# DClink.net
KiCad netlist of a schematic drawn in Altium Designer
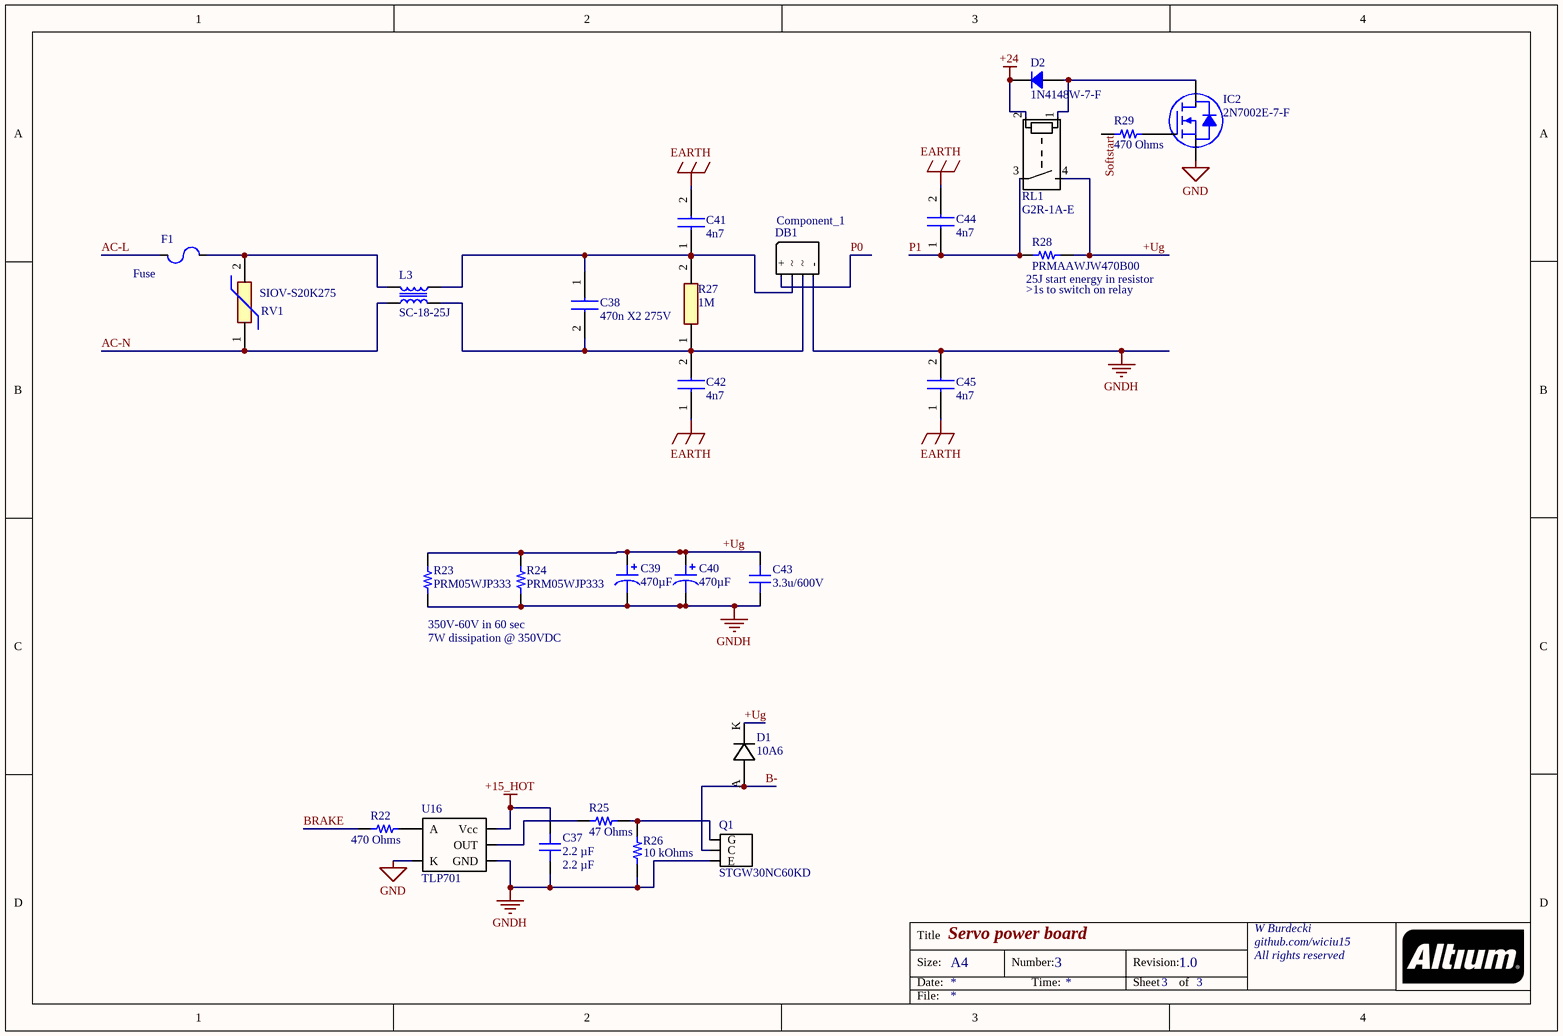
[diagram p0: DClink.SchDoc]

(export (version "E")
  (design (tool "Eeschema 10.0.6"))
  (components
    (comp (ref "C37")
      (value "2.2 µF")
      (footprint "CAP 0805_2012")
      (description "CAP CER 2.2UF 35V X7R 0805")
      (fields
        (field (name "PART NUMBER") "C2012X7R1V225K125AB")
        (field (name "ALTIUM_VALUE") "2.2 µF")
        (field (name "MANUFACTURER") "TDK Corporation")
      )
      (libsource (lib "Celestial") (part "Capacitor"))
    )
    (comp (ref "C38")
      (value "470n X2 275V")
      (footprint "SamacSys:R46KI347050M1K")
      (description "KEMET R46KI347050M1K")
      (fields
        (field (name "MANUFACTURER_PART_NUMBER") "R46KI347050M1K")
        (field (name "MOUSER PART NUMBER") "80-R46KI347050M1K")
      )
      (libsource (lib "*") (part "R46KI347050M1K"))
    )
    (comp (ref "C39")
      (value "470µF")
      (footprint "CAP TH ALUM ELEC D35.00mm S10.00mm H47.00mm")
      (description "CAP ALUM 470UF 20% 450V SNAP")
      (fields (field (name "PART NUMBER") "450HXG470MEFCSN35X45") (field (name "MANUFACTURER") "Rubycon"))
      (libsource (lib "Celestial") (part "Polarised Capacitor"))
    )
    (comp (ref "C40")
      (value "470µF")
      (footprint "CAP TH ALUM ELEC D35.00mm S10.00mm H47.00mm")
      (description "CAP ALUM 470UF 20% 450V SNAP")
      (fields (field (name "PART NUMBER") "450HXG470MEFCSN35X45") (field (name "MANUFACTURER") "Rubycon"))
      (libsource (lib "Celestial") (part "Polarised Capacitor"))
    )
    (comp (ref "C41")
      (value "4n7")
      (footprint "SamacSys:B32021_(13_x_5)")
      (description "B32021A3472")
      (fields
        (field (name "MANUFACTURER_PART_NUMBER") "B32021A3472K289")
        (field (name "MOUSER PART NUMBER") "871-B32021A3472K289")
      )
      (libsource (lib "*") (part "B32021A3472K289"))
    )
    (comp (ref "C42")
      (value "4n7")
      (footprint "SamacSys:B32021_(13_x_5)")
      (description "B32021A3472")
      (fields
        (field (name "MANUFACTURER_PART_NUMBER") "B32021A3472K289")
        (field (name "MOUSER PART NUMBER") "871-B32021A3472K289")
      )
      (libsource (lib "*") (part "B32021A3472K289"))
    )
    (comp (ref "C43")
      (value "3.3u/600V")
      (footprint "C4AQHBU4330P1WJ")
      (libsource (lib "C4AQHBU4330P1WJ") (part "3.3u/600V"))
    )
    (comp (ref "C44")
      (value "4n7")
      (footprint "SamacSys:B32021_(13_x_5)")
      (description "B32021A3472")
      (fields
        (field (name "MANUFACTURER_PART_NUMBER") "B32021A3472K289")
        (field (name "MOUSER PART NUMBER") "871-B32021A3472K289")
      )
      (libsource (lib "*") (part "B32021A3472K289"))
    )
    (comp (ref "C45")
      (value "4n7")
      (footprint "SamacSys:B32021_(13_x_5)")
      (description "B32021A3472")
      (fields
        (field (name "MANUFACTURER_PART_NUMBER") "B32021A3472K289")
        (field (name "MOUSER PART NUMBER") "871-B32021A3472K289")
      )
      (libsource (lib "*") (part "B32021A3472K289"))
    )
    (comp (ref "D1") (value "10A6") (footprint "10A6") (libsource (lib "10A6") (part "10A6")))
    (comp (ref "D2")
      (value "1N4148W-7-F")
      (footprint "SOD-123")
      (description "DIODE GEN PURP 100V 300MA SOD123")
      (fields (field (name "MANUFACTURER") "Diodes Incorporated"))
      (libsource (lib "Celestial") (part "Diode"))
    )
    (comp (ref "DB1")
      (value "Component_1")
      (footprint "GBJ2506")
      (libsource (lib "GBJ2506") (part "Component_1"))
    )
    (comp (ref "F1")
      (value "Fuse")
      (footprint "FUSE")
      (description "Fuse holder 04450001N")
      (libsource (lib "FUSE 04450001N") (part "Fuse"))
    )
    (comp (ref "IC2")
      (value "2N7002E-7-F")
      (footprint "DIODES SOT-23-3")
      (description "MOSFET N-CH 60V 0.25A SOT23-3")
      (fields (field (name "MANUFACTURER") "Diodes Incorporated"))
      (libsource (lib "Celestial") (part "DIODES INC MOSFET N-CH SOT-23-3"))
    )
    (comp (ref "L3")
      (value "SC-18-25J")
      (footprint "SC18-25J")
      (description "https://www.tme.eu/pl/details/sc-18-25j/dlawiki-pierscieniowe/kemet/")
      (libsource (lib "SC18-25J") (part "SC-18-25J"))
    )
    (comp (ref "Q1")
      (value "STGW30NC60KD")
      (footprint "STGW30NC60KD")
      (libsource (lib "STGW30NC60KD") (part "STGW30NC60KD"))
    )
    (comp (ref "R22")
      (value "470 Ohms")
      (footprint "RES 0805_2012")
      (description "RES SMD 470 OHM 0.1% 1/4W 0805")
      (fields
        (field (name "PART NUMBER") "ERJ-PB6B4700V")
        (field (name "MANUFACTURER") "Panasonic Electronic Components")
      )
      (libsource (lib "Celestial") (part "Resistor"))
    )
    (comp (ref "R23")
      (value "PRM05WJP333")
      (footprint "prmaawjw470b00")
      (libsource (lib "CRL5W-33k") (part "PRM05WJP333"))
    )
    (comp (ref "R24")
      (value "PRM05WJP333")
      (footprint "prmaawjw470b00")
      (libsource (lib "CRL5W-33k") (part "PRM05WJP333"))
    )
    (comp (ref "R25")
      (value "47 Ohms")
      (footprint "RES 0805_2012")
      (description "RES 47 OHM 1% 1/3W 0805")
      (fields
        (field (name "PART NUMBER") "CRGP0805F47R")
        (field (name "MANUFACTURER") "TE Connectivity Passive Product")
      )
      (libsource (lib "Celestial") (part "Resistor"))
    )
    (comp (ref "R26")
      (value "10 kOhms")
      (footprint "RES 0805_2012")
      (description "RES 10K OHM 0.1% 1/10W 0805")
      (fields
        (field (name "PART NUMBER") "RNCS0805BKE10K0")
        (field (name "MANUFACTURER") "Stackpole Electronics Inc")
      )
      (libsource (lib "Celestial") (part "Resistor"))
    )
    (comp (ref "R27")
      (value "1M")
      (footprint "SamacSys:RESAD2400W75L1000D350")
      (description "Resistor")
      (fields
        (field (name "MANUFACTURER_PART_NUMBER") "ROX1SJ330K")
        (field (name "MOUSER PART NUMBER") "279-ROX1SJ330K")
      )
      (libsource (lib "*") (part "ROX1SJ330K"))
    )
    (comp (ref "R28")
      (value "PRMAAWJW470B00")
      (footprint "prmaawjw470b00")
      (description "https://www.tme.eu/pl/details/ax10wv-47r/rezystory-mocy/royal-ohm/prmaawjw470b00/")
      (libsource (lib "prmaawjw470b00") (part "PRMAAWJW470B00"))
    )
    (comp (ref "R29")
      (value "470 Ohms")
      (footprint "RES 0805_2012")
      (description "RES SMD 470 OHM 0.1% 1/4W 0805")
      (fields
        (field (name "PART NUMBER") "ERJ-PB6B4700V")
        (field (name "MANUFACTURER") "Panasonic Electronic Components")
      )
      (libsource (lib "Celestial") (part "Resistor"))
    )
    (comp (ref "RL1")
      (value "G2R-1A-E")
      (footprint "G2R-1A-E")
      (libsource (lib "G2R-1A-E") (part "G2R-1A-E"))
    )
    (comp (ref "RV1")
      (value "SIOV-S20K275")
      (footprint "SamacSys:B72220Q0271K101")
      (description "B72220S0271K101")
      (fields
        (field (name "MANUFACTURER_PART_NUMBER") "B72220Q0271K101")
        (field (name "MOUSER PART NUMBER") "871-B72220Q271K101")
      )
      (libsource (lib "*") (part "B72220Q0271K101"))
    )
    (comp (ref "U16")
      (value "TLP701")
      (footprint "TLP701")
      (libsource (lib "Toshiba optocoupler") (part "TLP701"))
    )
  )
  (nets
    (net (code "1") (name "+15_HOT") (class "Default")
      (node (ref "C37") (pin "2") (pinfunction "2_2") (pintype "passive"))
      (node (ref "U16") (pin "6") (pinfunction "Vcc_6") (pintype "passive"))
    )
    (net (code "2") (name "+24") (class "Default")
      (node (ref "D2") (pin "2") (pinfunction "2_2") (pintype "passive"))
      (node (ref "RL1") (pin "2") (pinfunction "2_2") (pintype "passive"))
    )
    (net (code "3") (name "/+Ug") (class "Default")
      (node (ref "C39") (pin "1") (pinfunction "1_1") (pintype "passive"))
      (node (ref "C40") (pin "1") (pinfunction "1_1") (pintype "passive"))
      (node (ref "C43") (pin "2") (pinfunction "2_2") (pintype "passive"))
      (node (ref "D1") (pin "K") (pintype "passive"))
      (node (ref "R23") (pin "2") (pinfunction "2_2") (pintype "passive"))
      (node (ref "R24") (pin "2") (pinfunction "2_2") (pintype "passive"))
      (node (ref "R28") (pin "2") (pinfunction "2_2") (pintype "passive"))
      (node (ref "RL1") (pin "4") (pinfunction "4_4") (pintype "passive"))
    )
    (net (code "4") (name "/AC-L") (class "Default")
      (node (ref "F1") (pin "1") (pinfunction "1_1") (pintype "passive"))
    )
    (net (code "5") (name "/AC-N") (class "Default")
      (node (ref "L3") (pin "1") (pinfunction "1_1") (pintype "passive"))
      (node (ref "RV1") (pin "1") (pinfunction "1_1") (pintype "passive"))
    )
    (net (code "6") (name "/B-") (class "Default")
      (node (ref "D1") (pin "A") (pintype "passive"))
      (node (ref "Q1") (pin "2") (pinfunction "C_2") (pintype "passive"))
    )
    (net (code "7") (name "/BRAKE") (class "Default")
      (node (ref "R22") (pin "1") (pinfunction "1_1") (pintype "passive"))
    )
    (net (code "8") (name "/P0") (class "Default")
      (node (ref "DB1") (pin "1") (pinfunction "+_1") (pintype "passive"))
    )
    (net (code "9") (name "/P1") (class "Default")
      (node (ref "C44") (pin "1") (pinfunction "1_1") (pintype "passive"))
      (node (ref "R28") (pin "1") (pinfunction "1_1") (pintype "passive"))
      (node (ref "RL1") (pin "3") (pinfunction "3_3") (pintype "passive"))
    )
    (net (code "10") (name "/Softstart") (class "Default")
      (node (ref "R29") (pin "1") (pinfunction "1_1") (pintype "passive"))
    )
    (net (code "11") (name "EARTH") (class "Default")
      (node (ref "C41") (pin "2") (pinfunction "2_2") (pintype "passive"))
      (node (ref "C42") (pin "1") (pinfunction "1_1") (pintype "passive"))
      (node (ref "C44") (pin "2") (pinfunction "2_2") (pintype "passive"))
      (node (ref "C45") (pin "1") (pinfunction "1_1") (pintype "passive"))
    )
    (net (code "12") (name "GND") (class "Default")
      (node (ref "IC2") (pin "2") (pinfunction "S_2") (pintype "passive"))
      (node (ref "U16") (pin "3") (pinfunction "K_3") (pintype "passive"))
    )
    (net (code "13") (name "GNDH") (class "Default")
      (node (ref "C37") (pin "1") (pinfunction "1_1") (pintype "passive"))
      (node (ref "C39") (pin "2") (pinfunction "2_2") (pintype "passive"))
      (node (ref "C40") (pin "2") (pinfunction "2_2") (pintype "passive"))
      (node (ref "C43") (pin "1") (pinfunction "1_1") (pintype "passive"))
      (node (ref "C45") (pin "2") (pinfunction "2_2") (pintype "passive"))
      (node (ref "DB1") (pin "4") (pinfunction "-_4") (pintype "passive"))
      (node (ref "Q1") (pin "3") (pinfunction "E_3") (pintype "passive"))
      (node (ref "R23") (pin "1") (pinfunction "1_1") (pintype "passive"))
      (node (ref "R24") (pin "1") (pinfunction "1_1") (pintype "passive"))
      (node (ref "R26") (pin "1") (pinfunction "1_1") (pintype "passive"))
      (node (ref "U16") (pin "4") (pinfunction "GND_4") (pintype "passive"))
    )
    (net (code "14") (name "Net-(C38-Pad1)") (class "Default")
      (node (ref "C38") (pin "1") (pinfunction "1_1") (pintype "passive"))
      (node (ref "C41") (pin "1") (pinfunction "1_1") (pintype "passive"))
      (node (ref "DB1") (pin "2") (pinfunction "~_2") (pintype "passive"))
      (node (ref "L3") (pin "4") (pinfunction "4_4") (pintype "passive"))
      (node (ref "R27") (pin "2") (pinfunction "2_2") (pintype "passive"))
    )
    (net (code "15") (name "Net-(C38-Pad2)") (class "Default")
      (node (ref "C38") (pin "2") (pinfunction "2_2") (pintype "passive"))
      (node (ref "C42") (pin "2") (pinfunction "2_2") (pintype "passive"))
      (node (ref "DB1") (pin "3") (pinfunction "~_3") (pintype "passive"))
      (node (ref "L3") (pin "2") (pinfunction "2_2") (pintype "passive"))
      (node (ref "R27") (pin "1") (pinfunction "1_1") (pintype "passive"))
    )
    (net (code "16") (name "Net-(F1-Pad2)") (class "Default")
      (node (ref "F1") (pin "2") (pinfunction "2_2") (pintype "passive"))
      (node (ref "L3") (pin "3") (pinfunction "3_3") (pintype "passive"))
      (node (ref "RV1") (pin "2") (pinfunction "2_2") (pintype "passive"))
    )
    (net (code "17") (name "Net-(IC2-D)") (class "Default")
      (node (ref "D2") (pin "1") (pinfunction "1_1") (pintype "passive"))
      (node (ref "IC2") (pin "3") (pinfunction "D_3") (pintype "passive"))
      (node (ref "RL1") (pin "1") (pinfunction "1_1") (pintype "passive"))
    )
    (net (code "18") (name "Net-(IC2-G)") (class "Default")
      (node (ref "IC2") (pin "1") (pinfunction "G_1") (pintype "passive"))
      (node (ref "R29") (pin "2") (pinfunction "2_2") (pintype "passive"))
    )
    (net (code "19") (name "Net-(Q1-G)") (class "Default")
      (node (ref "Q1") (pin "1") (pinfunction "G_1") (pintype "passive"))
      (node (ref "R25") (pin "2") (pinfunction "2_2") (pintype "passive"))
      (node (ref "R26") (pin "2") (pinfunction "2_2") (pintype "passive"))
    )
    (net (code "20") (name "Net-(U16-A)") (class "Default")
      (node (ref "R22") (pin "2") (pinfunction "2_2") (pintype "passive"))
      (node (ref "U16") (pin "1") (pinfunction "A_1") (pintype "passive"))
    )
    (net (code "21") (name "Net-(U16-OUT)") (class "Default")
      (node (ref "R25") (pin "1") (pinfunction "1_1") (pintype "passive"))
      (node (ref "U16") (pin "5") (pinfunction "OUT_5") (pintype "passive"))
    )
  )
)
